# SCH_Switch.net
KiCad netlist of a schematic drawn in Altium Designer
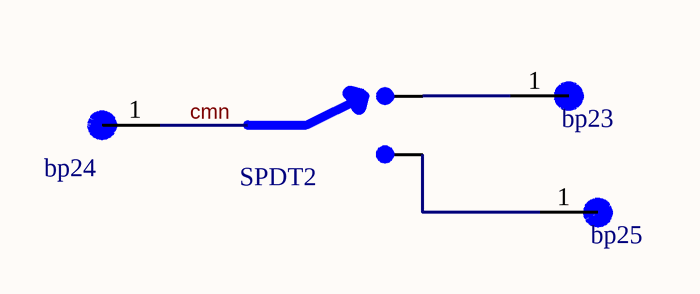
[diagram p0: SCH_Switch.SchDoc]

(export (version "E")
  (design (tool "Eeschema 10.0.6"))
  (components
    (comp (ref "bp23")
      (value "Board Pad")
      (footprint "Battery pad")
      (libsource (lib "Schlib1") (part "Board Pad"))
    )
    (comp (ref "bp24")
      (value "Board Pad")
      (footprint "Battery pad")
      (libsource (lib "Schlib1") (part "Board Pad"))
    )
    (comp (ref "bp25")
      (value "Board Pad")
      (footprint "Battery pad")
      (libsource (lib "Schlib1") (part "Board Pad"))
    )
    (comp (ref "SPDT2")
      (value "spdt_JS202011SCQN")
      (footprint "SPDT_1")
      (description "C & K COMPONENTS - JS202011SCQN - SWITCH, DPDT, 0.6A, 6VDC, SMD")
      (fields (field (name "MANUFACTURER") "ITT C&K"))
      (libsource (lib "Schlib1") (part "spdt_JS202011SCQN"))
    )
  )
  (nets
    (net (code "1") (name "/cmn") (class "Default")
      (node (ref "SPDT2") (pin "1") (pinfunction "1_1") (pintype "passive"))
      (node (ref "bp24") (pin "1") (pinfunction "1_1") (pintype "passive"))
    )
    (net (code "2") (name "Net-(SPDT2-Pad2)") (class "Default")
      (node (ref "SPDT2") (pin "2") (pinfunction "2_2") (pintype "passive"))
      (node (ref "bp23") (pin "1") (pinfunction "1_1") (pintype "passive"))
    )
    (net (code "3") (name "Net-(SPDT2-Pad3)") (class "Default")
      (node (ref "SPDT2") (pin "3") (pinfunction "3_3") (pintype "passive"))
      (node (ref "bp25") (pin "1") (pinfunction "1_1") (pintype "passive"))
    )
  )
)
